# MIS_Locker_old.net
KiCad netlist of a schematic drawn in Altium Designer
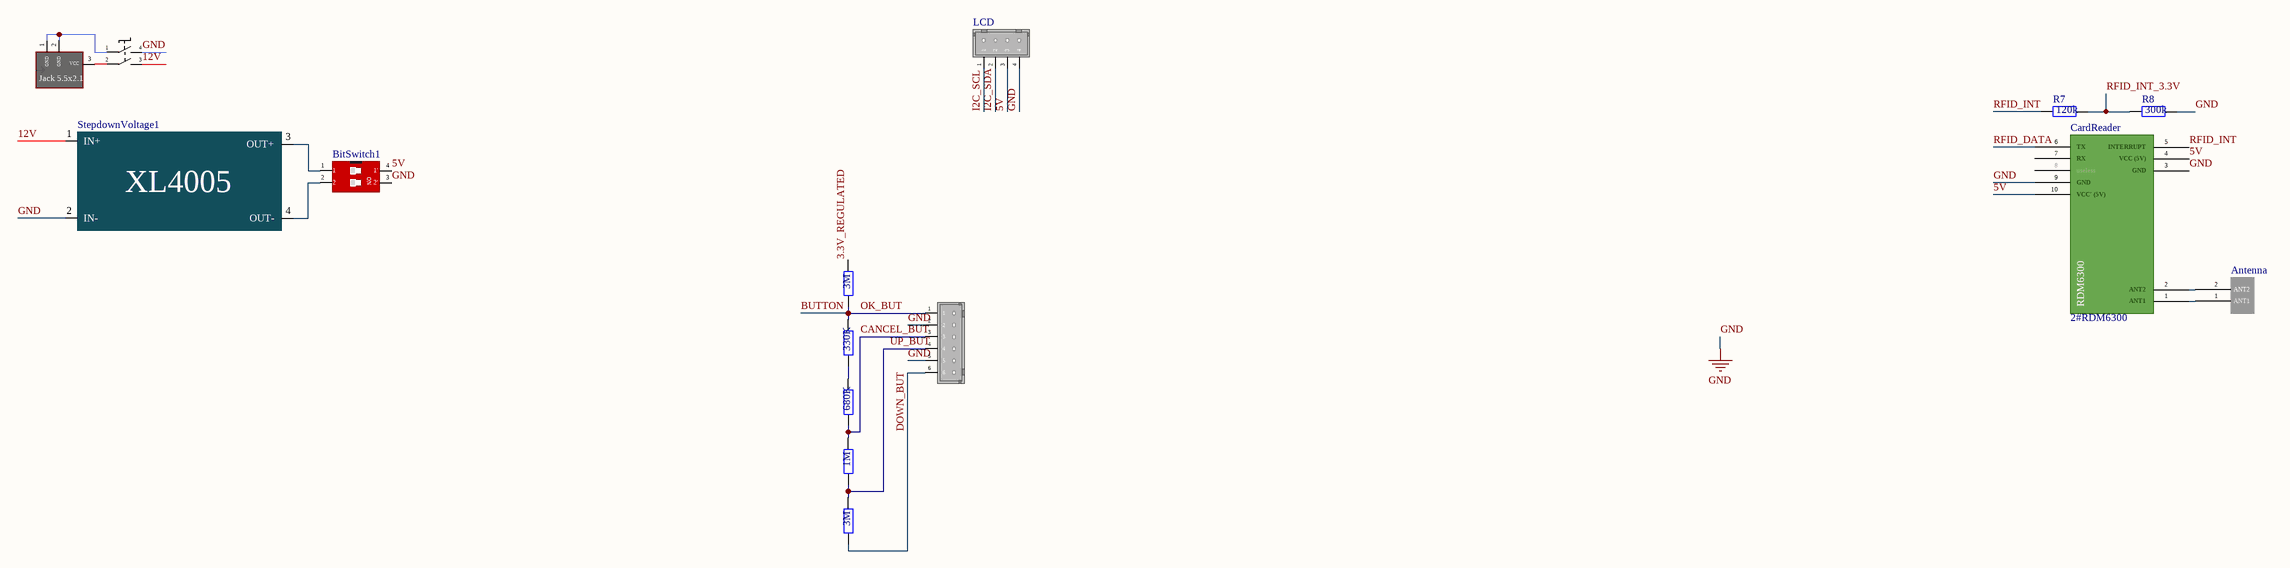
[diagram p0: MIS_Locker_old.SchDoc]

(export (version "E")
  (design (tool "Eeschema 10.0.6"))
  (components
    (comp (ref "Antenna")
      (value "2#RDM6300_Magnetic_Coil")
      (footprint "2#RDM6300_Magnetic_Coil")
      (libsource (lib "Sch") (part "2#RDM6300_Magnetic_Coil"))
    )
    (comp (ref "BitSwitch1")
      (value "5#Bit_Switch_2")
      (footprint "5#Bit_Switch_2")
      (libsource (lib "Sch") (part "5#Bit_Switch_2"))
    )
    (comp (ref "Button")
      (value "5#Jack6_Button")
      (footprint "5#Jack6_Button")
      (libsource (lib "Sch") (part "5#Jack6_Button"))
    )
    (comp (ref "CardReader")
      (value "2#RDM6300")
      (footprint "2#RDM6300")
      (libsource (lib "Sch") (part "2#RDM6300"))
    )
    (comp (ref "J1")
      (value "5#DC Jack 2.54mm")
      (footprint "5#DC Jack 2.54mm")
      (libsource (lib "Sch") (part "5#DC Jack 2.54mm"))
    )
    (comp (ref "LCD")
      (value "5#Jack4_LCD")
      (footprint "5#Jack4_LCD")
      (libsource (lib "Sch") (part "5#Jack4_LCD"))
    )
    (comp (ref "PowerSwitchHole1")
      (value "5#PowerSwitchHole")
      (footprint "5#PowerSwitchHole")
      (libsource (lib "Sch") (part "5#PowerSwitchHole"))
    )
    (comp (ref "R7")
      (value "120k")
      (footprint "AXIAL-0.4")
      (description "Resistor")
      (fields (field (name "PUBLISHER") "Altium Limited"))
      (libsource (lib "") (part "Res2_1"))
    )
    (comp (ref "R8")
      (value "300k")
      (footprint "AXIAL-0.4")
      (description "Resistor")
      (fields (field (name "PUBLISHER") "Altium Limited"))
      (libsource (lib "") (part "Res2_1"))
    )
    (comp (ref "R13")
      (value "3M")
      (footprint "AXIAL-0.4")
      (description "Resistor")
      (fields (field (name "PUBLISHER") "Altium Limited"))
      (libsource (lib "Miscellaneous Devices") (part "Res2"))
    )
    (comp (ref "R14")
      (value "330K")
      (footprint "AXIAL-0.4")
      (description "Resistor")
      (fields (field (name "PUBLISHER") "Altium Limited"))
      (libsource (lib "Miscellaneous Devices") (part "Res2"))
    )
    (comp (ref "R15")
      (value "680K")
      (footprint "AXIAL-0.4")
      (description "Resistor")
      (fields (field (name "PUBLISHER") "Altium Limited"))
      (libsource (lib "Miscellaneous Devices") (part "Res2"))
    )
    (comp (ref "R16")
      (value "1M")
      (footprint "AXIAL-0.4")
      (description "Resistor")
      (fields (field (name "PUBLISHER") "Altium Limited"))
      (libsource (lib "Miscellaneous Devices") (part "Res2"))
    )
    (comp (ref "R17")
      (value "3M")
      (footprint "AXIAL-0.4")
      (description "Resistor")
      (fields (field (name "PUBLISHER") "Altium Limited"))
      (libsource (lib "Miscellaneous Devices") (part "Res2"))
    )
    (comp (ref "StepdownVoltage1")
      (value "5#Stepdown_XL4005")
      (footprint "5#Stepdown_XL4005")
      (libsource (lib "Sch") (part "5#Stepdown_XL4005"))
    )
  )
  (nets
    (net (code "1") (name "/3.3V_REGULATED") (class "Default")
      (node (ref "R13") (pin "1") (pinfunction "1_1") (pintype "passive"))
    )
    (net (code "2") (name "/5V") (class "Default")
      (node (ref "BitSwitch1") (pin "4") (pinfunction "1'_4") (pintype "passive"))
      (node (ref "CardReader") (pin "10") (pinfunction "VCC'_(5V)_10") (pintype "passive"))
      (node (ref "CardReader") (pin "4") (pinfunction "VCC_(5V)_4") (pintype "power_in"))
      (node (ref "LCD") (pin "3") (pinfunction "3_3") (pintype "passive"))
    )
    (net (code "3") (name "/12V") (class "Default")
      (node (ref "PowerSwitchHole1") (pin "3") (pinfunction "3_3") (pintype "passive"))
      (node (ref "StepdownVoltage1") (pin "1") (pinfunction "IN+_1") (pintype "passive"))
    )
    (net (code "4") (name "/BUTTON") (class "Default")
      (node (ref "Button") (pin "1") (pinfunction "1_1") (pintype "passive"))
      (node (ref "R13") (pin "2") (pinfunction "2_2") (pintype "passive"))
      (node (ref "R14") (pin "1") (pinfunction "1_1") (pintype "passive"))
    )
    (net (code "5") (name "/CANCEL_BUT") (class "Default")
      (node (ref "Button") (pin "3") (pinfunction "3_3") (pintype "passive"))
      (node (ref "R15") (pin "2") (pinfunction "2_2") (pintype "passive"))
      (node (ref "R16") (pin "1") (pinfunction "1_1") (pintype "passive"))
    )
    (net (code "6") (name "/DOWN_BUT") (class "Default")
      (node (ref "Button") (pin "6") (pinfunction "6_6") (pintype "passive"))
      (node (ref "R17") (pin "2") (pinfunction "2_2") (pintype "passive"))
    )
    (net (code "7") (name "/I2C_SCL") (class "Default")
      (node (ref "LCD") (pin "1") (pinfunction "1_1") (pintype "passive"))
    )
    (net (code "8") (name "/I2C_SDA") (class "Default")
      (node (ref "LCD") (pin "2") (pinfunction "2_2") (pintype "passive"))
    )
    (net (code "9") (name "/RFID_DATA") (class "Default")
      (node (ref "CardReader") (pin "6") (pinfunction "TX_6") (pintype "passive"))
    )
    (net (code "10") (name "/RFID_INT") (class "Default")
      (node (ref "CardReader") (pin "5") (pinfunction "INTERRUPT_5") (pintype "passive"))
      (node (ref "R7") (pin "2") (pinfunction "2_2") (pintype "passive"))
    )
    (net (code "11") (name "/RFID_INT_3.3V") (class "Default")
      (node (ref "R7") (pin "1") (pinfunction "1_1") (pintype "passive"))
      (node (ref "R8") (pin "2") (pinfunction "2_2") (pintype "passive"))
    )
    (net (code "12") (name "/UP_BUT") (class "Default")
      (node (ref "Button") (pin "4") (pinfunction "4_4") (pintype "passive"))
      (node (ref "R16") (pin "2") (pinfunction "2_2") (pintype "passive"))
      (node (ref "R17") (pin "1") (pinfunction "1_1") (pintype "passive"))
    )
    (net (code "13") (name "GND") (class "Default")
      (node (ref "BitSwitch1") (pin "3") (pinfunction "2'_3") (pintype "passive"))
      (node (ref "Button") (pin "2") (pinfunction "2_2") (pintype "passive"))
      (node (ref "Button") (pin "5") (pinfunction "5_5") (pintype "passive"))
      (node (ref "CardReader") (pin "3") (pinfunction "GND_3") (pintype "passive"))
      (node (ref "CardReader") (pin "9") (pinfunction "GND_9") (pintype "passive"))
      (node (ref "LCD") (pin "4") (pinfunction "4_4") (pintype "passive"))
      (node (ref "PowerSwitchHole1") (pin "4") (pinfunction "3_4") (pintype "passive"))
      (node (ref "R8") (pin "1") (pinfunction "1_1") (pintype "passive"))
      (node (ref "StepdownVoltage1") (pin "2") (pinfunction "IN-_2") (pintype "passive"))
    )
    (net (code "14") (name "Net-(Antenna-ANT1)") (class "Default")
      (node (ref "Antenna") (pin "1") (pinfunction "ANT1_1") (pintype "passive"))
      (node (ref "CardReader") (pin "1") (pinfunction "ANT1_1") (pintype "power_in"))
    )
    (net (code "15") (name "Net-(Antenna-ANT2)") (class "Default")
      (node (ref "Antenna") (pin "2") (pinfunction "ANT2_2") (pintype "passive"))
      (node (ref "CardReader") (pin "2") (pinfunction "ANT2_2") (pintype "passive"))
    )
    (net (code "16") (name "Net-(J1-GND-Pad1)") (class "Default")
      (node (ref "J1") (pin "1") (pinfunction "GND_1") (pintype "passive"))
      (node (ref "J1") (pin "2") (pinfunction "GND_2") (pintype "passive"))
      (node (ref "PowerSwitchHole1") (pin "1") (pinfunction "1_1") (pintype "passive"))
    )
    (net (code "17") (name "Net-(J1-VCC)") (class "Default")
      (node (ref "J1") (pin "3") (pinfunction "VCC_3") (pintype "passive"))
      (node (ref "PowerSwitchHole1") (pin "2") (pinfunction "2_2") (pintype "passive"))
    )
    (net (code "18") (name "Net-(R14-Pad2)") (class "Default")
      (node (ref "R14") (pin "2") (pinfunction "2_2") (pintype "passive"))
      (node (ref "R15") (pin "1") (pinfunction "1_1") (pintype "passive"))
    )
    (net (code "19") (name "Net-(StepdownVoltage1-OUT+)") (class "Default")
      (node (ref "BitSwitch1") (pin "1") (pinfunction "1_1") (pintype "passive"))
      (node (ref "StepdownVoltage1") (pin "3") (pinfunction "OUT+_3") (pintype "passive"))
    )
    (net (code "20") (name "Net-(StepdownVoltage1-OUT-)") (class "Default")
      (node (ref "BitSwitch1") (pin "2") (pinfunction "2_2") (pintype "passive"))
      (node (ref "StepdownVoltage1") (pin "4") (pinfunction "OUT-_4") (pintype "passive"))
    )
    (net (code "21") (name "unconnected-(CardReader-RX-Pad7)") (class "Default")
      (node (ref "CardReader") (pin "7") (pinfunction "RX_7") (pintype "passive"))
    )
    (net (code "22") (name "unconnected-(CardReader-useless-Pad8)") (class "Default")
      (node (ref "CardReader") (pin "8") (pinfunction "useless_8") (pintype "passive"))
    )
  )
)
